# Arduino_HAT.net
KiCad netlist of a schematic drawn in EAGLE
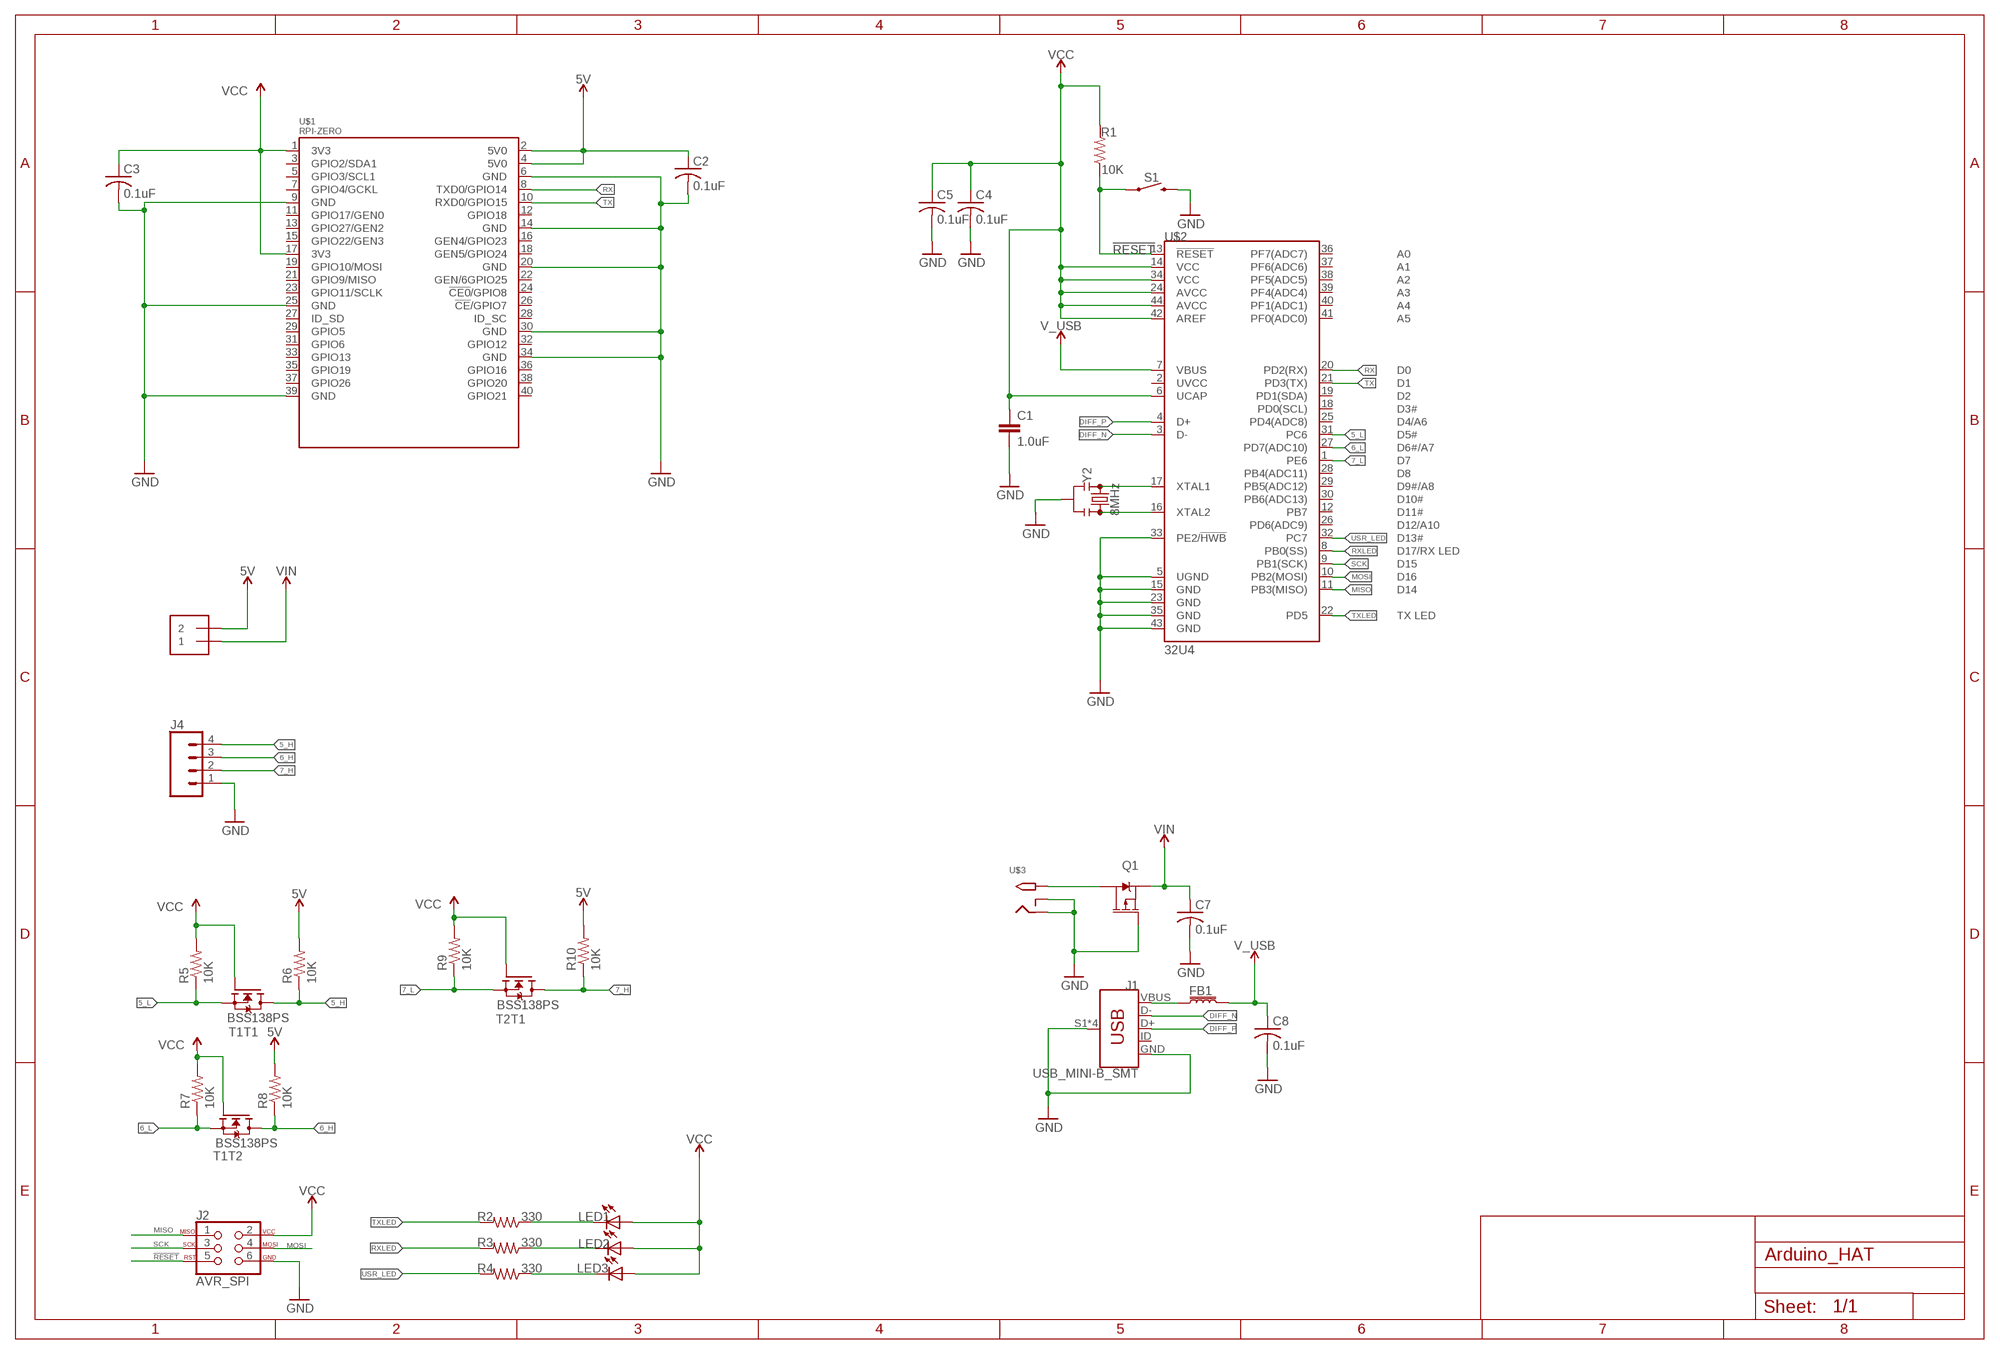
[diagram p0: schematic, sheet 1]

(export (version "E")
  (design (tool "Eeschema 10.0.6"))
  (components
    (comp (ref "C1")
      (value "1.0uF")
      (footprint "eagle-import:0805")
      (libsource (lib "eagle-import") (part "1.0UF-0805-25V-10%"))
    )
    (comp (ref "C2")
      (value "0.1uF")
      (footprint "eagle-import:C0805")
      (libsource (lib "eagle-import") (part "C-USC0805"))
    )
    (comp (ref "C3")
      (value "0.1uF")
      (footprint "eagle-import:C0805")
      (libsource (lib "eagle-import") (part "C-USC0805"))
    )
    (comp (ref "C4")
      (value "0.1uF")
      (footprint "eagle-import:C0805")
      (libsource (lib "eagle-import") (part "C-USC0805"))
    )
    (comp (ref "C5")
      (value "0.1uF")
      (footprint "eagle-import:C0805")
      (libsource (lib "eagle-import") (part "C-USC0805"))
    )
    (comp (ref "C7")
      (value "0.1uF")
      (footprint "eagle-import:C0805")
      (libsource (lib "eagle-import") (part "C-USC0805"))
    )
    (comp (ref "C8")
      (value "0.1uF")
      (footprint "eagle-import:C0805")
      (libsource (lib "eagle-import") (part "C-USC0805"))
    )
    (comp (ref "FB1")
      (value "30Ω/1.8A")
      (footprint "eagle-import:0603")
      (libsource (lib "eagle-import") (part "FERRITE_BEAD-0603"))
    )
    (comp (ref "J1")
      (value "USB_MINI-B_SMT")
      (footprint "eagle-import:USB-MINIB")
      (libsource (lib "eagle-import") (part "USB_MINI-B_SMT"))
    )
    (comp (ref "J2")
      (value "AVR_SPI")
      (footprint "eagle-import:2X3-NS")
      (libsource (lib "eagle-import") (part "AVR_SPI_PROG_3X2NS"))
    )
    (comp (ref "J3")
      (value "1X2-3.5MM")
      (footprint "eagle-import:1X2-3.5MM")
      (libsource (lib "eagle-import") (part "1X2-3.5MM"))
    )
    (comp (ref "J4")
      (value "CONN_04SCREW")
      (footprint "eagle-import:SCREWTERMINAL-3.5MM-4")
      (libsource (lib "eagle-import") (part "CONN_04SCREW"))
    )
    (comp (ref "LED1")
      (value "LEDCHIPLED_0805")
      (footprint "eagle-import:CHIPLED_0805")
      (libsource (lib "eagle-import") (part "LEDCHIPLED_0805"))
    )
    (comp (ref "LED2")
      (value "LEDCHIPLED_0805")
      (footprint "eagle-import:CHIPLED_0805")
      (libsource (lib "eagle-import") (part "LEDCHIPLED_0805"))
    )
    (comp (ref "LED3")
      (value "LEDCHIPLED_0805")
      (footprint "eagle-import:CHIPLED_0805")
      (libsource (lib "eagle-import") (part "LEDCHIPLED_0805"))
    )
    (comp (ref "Q1")
      (value "2.5A/30V/105mΩ")
      (footprint "eagle-import:SOT23-3")
      (libsource (lib "eagle-import") (part "MOSFET_PCH-DMG2307L"))
    )
    (comp (ref "R1")
      (value "10K")
      (footprint "eagle-import:0805")
      (libsource (lib "eagle-import") (part "RESISTOR0805"))
    )
    (comp (ref "R2")
      (value "330")
      (footprint "eagle-import:0805")
      (libsource (lib "eagle-import") (part "RESISTOR0805"))
    )
    (comp (ref "R3")
      (value "330")
      (footprint "eagle-import:0805")
      (libsource (lib "eagle-import") (part "RESISTOR0805"))
    )
    (comp (ref "R4")
      (value "330")
      (footprint "eagle-import:0805")
      (libsource (lib "eagle-import") (part "RESISTOR0805"))
    )
    (comp (ref "R5")
      (value "10K")
      (footprint "eagle-import:R0805")
      (libsource (lib "eagle-import") (part "R-US_R0805"))
    )
    (comp (ref "R6")
      (value "10K")
      (footprint "eagle-import:R0805")
      (libsource (lib "eagle-import") (part "R-US_R0805"))
    )
    (comp (ref "R7")
      (value "10K")
      (footprint "eagle-import:R0805")
      (libsource (lib "eagle-import") (part "R-US_R0805"))
    )
    (comp (ref "R8")
      (value "10K")
      (footprint "eagle-import:R0805")
      (libsource (lib "eagle-import") (part "R-US_R0805"))
    )
    (comp (ref "R9")
      (value "10K")
      (footprint "eagle-import:R0805")
      (libsource (lib "eagle-import") (part "R-US_R0805"))
    )
    (comp (ref "R10")
      (value "10K")
      (footprint "eagle-import:R0805")
      (libsource (lib "eagle-import") (part "R-US_R0805"))
    )
    (comp (ref "S1")
      (value "MOMENTARY-SWITCH-SPST-SMD-4.6X2.8MM")
      (footprint "eagle-import:TACTILE_SWITCH_SMD_4.6X2.8MM")
      (libsource (lib "eagle-import") (part "MOMENTARY-SWITCH-SPST-SMD-4.6X2.8MM"))
    )
    (comp (ref "T1")
      (value "BSS138PS")
      (footprint "eagle-import:SOT363")
      (libsource (lib "eagle-import") (part "BSS138PS"))
    )
    (comp (ref "T2")
      (value "BSS138PS")
      (footprint "eagle-import:SOT363")
      (libsource (lib "eagle-import") (part "BSS138PS"))
    )
    (comp (ref "U$1")
      (value "RPI-ZERO")
      (footprint "eagle-import:RASPBERRYPI_BASTELSTUBE_V13_RASPI_BOARD_B+_FULL")
      (libsource (lib "eagle-import") (part "RPI-ZERO"))
    )
    (comp (ref "U$2")
      (value "32U4")
      (footprint "eagle-import:QFN-44")
      (libsource (lib "eagle-import") (part "ATMEGA32U4QFN"))
    )
    (comp (ref "U$3")
      (value "2.1MMJACKTHM")
      (footprint "eagle-import:PJ-102A")
      (libsource (lib "eagle-import") (part "2.1MMJACKTHM"))
    )
    (comp (ref "Y2")
      (value "8MHz")
      (footprint "eagle-import:RESONATOR-SMD-3.2X1.3")
      (libsource (lib "eagle-import") (part "RESONATOR-8MHZSMD_3.2X1.3"))
    )
  )
  (nets
    (net (code "1") (name "/~{RESET}") (class "Default")
      (node (ref "J2") (pin "5") (pinfunction "5_5") (pintype "passive"))
      (node (ref "R1") (pin "1") (pinfunction "1_1") (pintype "passive"))
      (node (ref "S1") (pin "1") (pinfunction "1_1") (pintype "passive"))
      (node (ref "S1") (pin "2") (pinfunction "1_2") (pintype "passive"))
      (node (ref "U$2") (pin "13") (pinfunction "~{RESET}_13") (pintype "bidirectional"))
    )
    (net (code "2") (name "5V") (class "Default")
      (node (ref "C2") (pin "1") (pinfunction "1_1") (pintype "passive"))
      (node (ref "J3") (pin "2") (pinfunction "2_2") (pintype "passive"))
      (node (ref "R10") (pin "2") (pinfunction "2_2") (pintype "passive"))
      (node (ref "R6") (pin "2") (pinfunction "2_2") (pintype "passive"))
      (node (ref "R8") (pin "2") (pinfunction "2_2") (pintype "passive"))
      (node (ref "U$1") (pin "2") (pinfunction "5V0_2") (pintype "power_in"))
      (node (ref "U$1") (pin "4") (pinfunction "5V0_4") (pintype "power_in"))
    )
    (net (code "3") (name "5_H") (class "Default")
      (node (ref "J4") (pin "4") (pinfunction "GND_4") (pintype "passive"))
      (node (ref "R6") (pin "1") (pinfunction "1_1") (pintype "passive"))
      (node (ref "T1") (pin "6") (pinfunction "D_6") (pintype "passive"))
    )
    (net (code "4") (name "5_L") (class "Default")
      (node (ref "R5") (pin "1") (pinfunction "1_1") (pintype "passive"))
      (node (ref "T1") (pin "1") (pinfunction "S_1") (pintype "passive"))
      (node (ref "U$2") (pin "31") (pinfunction "PC6_31") (pintype "bidirectional"))
    )
    (net (code "5") (name "6_H") (class "Default")
      (node (ref "J4") (pin "3") (pinfunction "SDA_3") (pintype "passive"))
      (node (ref "R8") (pin "1") (pinfunction "1_1") (pintype "passive"))
      (node (ref "T1") (pin "3") (pinfunction "D_3") (pintype "passive"))
    )
    (net (code "6") (name "6_L") (class "Default")
      (node (ref "R7") (pin "1") (pinfunction "1_1") (pintype "passive"))
      (node (ref "T1") (pin "4") (pinfunction "S_4") (pintype "passive"))
      (node (ref "U$2") (pin "27") (pinfunction "PD7(ADC10)_27") (pintype "bidirectional"))
    )
    (net (code "7") (name "7_H") (class "Default")
      (node (ref "J4") (pin "2") (pinfunction "SCL_2") (pintype "passive"))
      (node (ref "R10") (pin "1") (pinfunction "1_1") (pintype "passive"))
      (node (ref "T2") (pin "6") (pinfunction "D_6") (pintype "passive"))
    )
    (net (code "8") (name "7_L") (class "Default")
      (node (ref "R9") (pin "1") (pinfunction "1_1") (pintype "passive"))
      (node (ref "T2") (pin "1") (pinfunction "S_1") (pintype "passive"))
      (node (ref "U$2") (pin "1") (pinfunction "PE6_1") (pintype "bidirectional"))
    )
    (net (code "9") (name "DIFF_N") (class "Default")
      (node (ref "J1") (pin "D-") (pinfunction "D-_D-") (pintype "bidirectional"))
      (node (ref "U$2") (pin "3") (pinfunction "D-_3") (pintype "bidirectional"))
    )
    (net (code "10") (name "DIFF_P") (class "Default")
      (node (ref "J1") (pin "D+") (pinfunction "D+_D+") (pintype "bidirectional"))
      (node (ref "U$2") (pin "4") (pinfunction "D+_4") (pintype "bidirectional"))
    )
    (net (code "11") (name "GND") (class "Default")
      (node (ref "C1") (pin "2") (pinfunction "2_2") (pintype "passive"))
      (node (ref "C2") (pin "2") (pinfunction "2_2") (pintype "passive"))
      (node (ref "C3") (pin "2") (pinfunction "2_2") (pintype "passive"))
      (node (ref "C4") (pin "2") (pinfunction "2_2") (pintype "passive"))
      (node (ref "C5") (pin "2") (pinfunction "2_2") (pintype "passive"))
      (node (ref "C7") (pin "2") (pinfunction "2_2") (pintype "passive"))
      (node (ref "C8") (pin "2") (pinfunction "2_2") (pintype "passive"))
      (node (ref "J1") (pin "GND") (pinfunction "GND_GND") (pintype "power_in"))
      (node (ref "J1") (pin "S1") (pinfunction "SHIELD_S1") (pintype "bidirectional"))
      (node (ref "J1") (pin "S2") (pinfunction "SHIELD_S2") (pintype "bidirectional"))
      (node (ref "J1") (pin "S3") (pinfunction "SHIELD_S3") (pintype "bidirectional"))
      (node (ref "J1") (pin "S4") (pinfunction "SHIELD_S4") (pintype "bidirectional"))
      (node (ref "J2") (pin "6") (pinfunction "6_6") (pintype "passive"))
      (node (ref "J4") (pin "1") (pinfunction "VCC_1") (pintype "passive"))
      (node (ref "Q1") (pin "1") (pinfunction "G_1") (pintype "bidirectional"))
      (node (ref "S1") (pin "3") (pinfunction "2_3") (pintype "passive"))
      (node (ref "S1") (pin "4") (pinfunction "2_4") (pintype "passive"))
      (node (ref "U$1") (pin "14") (pinfunction "GND_14") (pintype "power_in"))
      (node (ref "U$1") (pin "20") (pinfunction "GND_20") (pintype "power_in"))
      (node (ref "U$1") (pin "25") (pinfunction "GND_25") (pintype "power_in"))
      (node (ref "U$1") (pin "30") (pinfunction "GND_30") (pintype "power_in"))
      (node (ref "U$1") (pin "34") (pinfunction "GND_34") (pintype "power_in"))
      (node (ref "U$1") (pin "39") (pinfunction "GND_39") (pintype "power_in"))
      (node (ref "U$1") (pin "6") (pinfunction "GND_6") (pintype "power_in"))
      (node (ref "U$1") (pin "9") (pinfunction "GND_9") (pintype "power_in"))
      (node (ref "U$2") (pin "15") (pinfunction "GND_15") (pintype "bidirectional"))
      (node (ref "U$2") (pin "23") (pinfunction "GND_23") (pintype "bidirectional"))
      (node (ref "U$2") (pin "33") (pinfunction "PE2/~{HWB}_33") (pintype "bidirectional"))
      (node (ref "U$2") (pin "35") (pinfunction "GND_35") (pintype "bidirectional"))
      (node (ref "U$2") (pin "43") (pinfunction "GND_43") (pintype "bidirectional"))
      (node (ref "U$2") (pin "5") (pinfunction "UGND_5") (pintype "bidirectional"))
      (node (ref "U$3") (pin "RING") (pinfunction "RING_RING") (pintype "bidirectional"))
      (node (ref "U$3") (pin "RING_SW") (pinfunction "RING_SW_RING_SW") (pintype "bidirectional"))
      (node (ref "Y2") (pin "2") (pinfunction "2_2") (pintype "passive"))
    )
    (net (code "12") (name "MISO") (class "Default")
      (node (ref "J2") (pin "1") (pinfunction "1_1") (pintype "passive"))
      (node (ref "U$2") (pin "11") (pinfunction "PB3(MISO)_11") (pintype "bidirectional"))
    )
    (net (code "13") (name "MOSI") (class "Default")
      (node (ref "J2") (pin "4") (pinfunction "4_4") (pintype "passive"))
      (node (ref "U$2") (pin "10") (pinfunction "PB2(MOSI)_10") (pintype "bidirectional"))
    )
    (net (code "14") (name "Net-(FB1-Pad1)") (class "Default")
      (node (ref "FB1") (pin "1") (pinfunction "1_1") (pintype "passive"))
      (node (ref "J1") (pin "VBUS") (pinfunction "VBUS_VBUS") (pintype "power_in"))
    )
    (net (code "15") (name "Net-(LED1-PadC)") (class "Default")
      (node (ref "LED1") (pin "C") (pinfunction "C_C") (pintype "passive"))
      (node (ref "R2") (pin "1") (pinfunction "1_1") (pintype "passive"))
    )
    (net (code "16") (name "Net-(LED2-PadC)") (class "Default")
      (node (ref "LED2") (pin "C") (pinfunction "C_C") (pintype "passive"))
      (node (ref "R3") (pin "1") (pinfunction "1_1") (pintype "passive"))
    )
    (net (code "17") (name "Net-(LED3-PadC)") (class "Default")
      (node (ref "LED3") (pin "C") (pinfunction "C_C") (pintype "passive"))
      (node (ref "R4") (pin "1") (pinfunction "1_1") (pintype "passive"))
    )
    (net (code "18") (name "Net-(Q1-D)") (class "Default")
      (node (ref "Q1") (pin "3") (pinfunction "D_3") (pintype "bidirectional"))
      (node (ref "U$3") (pin "TIP") (pinfunction "TIP_TIP") (pintype "bidirectional"))
    )
    (net (code "19") (name "Net-(U$2-XTAL1)") (class "Default")
      (node (ref "U$2") (pin "17") (pinfunction "XTAL1_17") (pintype "bidirectional"))
      (node (ref "Y2") (pin "1") (pinfunction "1_1") (pintype "passive"))
    )
    (net (code "20") (name "Net-(U$2-XTAL2)") (class "Default")
      (node (ref "U$2") (pin "16") (pinfunction "XTAL2_16") (pintype "bidirectional"))
      (node (ref "Y2") (pin "3") (pinfunction "3_3") (pintype "passive"))
    )
    (net (code "21") (name "RX") (class "Default")
      (node (ref "U$1") (pin "8") (pinfunction "TXD0/GPIO14_8") (pintype "bidirectional"))
      (node (ref "U$2") (pin "20") (pinfunction "PD2(RX)_20") (pintype "bidirectional"))
    )
    (net (code "22") (name "RXLED") (class "Default")
      (node (ref "R3") (pin "2") (pinfunction "2_2") (pintype "passive"))
      (node (ref "U$2") (pin "8") (pinfunction "PB0(SS)_8") (pintype "bidirectional"))
    )
    (net (code "23") (name "SCK") (class "Default")
      (node (ref "J2") (pin "3") (pinfunction "3_3") (pintype "passive"))
      (node (ref "U$2") (pin "9") (pinfunction "PB1(SCK)_9") (pintype "bidirectional"))
    )
    (net (code "24") (name "TX") (class "Default")
      (node (ref "U$1") (pin "10") (pinfunction "RXD0/GPIO15_10") (pintype "bidirectional"))
      (node (ref "U$2") (pin "21") (pinfunction "PD3(TX)_21") (pintype "bidirectional"))
    )
    (net (code "25") (name "TXLED") (class "Default")
      (node (ref "R2") (pin "2") (pinfunction "2_2") (pintype "passive"))
      (node (ref "U$2") (pin "22") (pinfunction "PD5_22") (pintype "bidirectional"))
    )
    (net (code "26") (name "USR_LED") (class "Default")
      (node (ref "R4") (pin "2") (pinfunction "2_2") (pintype "passive"))
      (node (ref "U$2") (pin "32") (pinfunction "PC7_32") (pintype "bidirectional"))
    )
    (net (code "27") (name "VCC") (class "Default")
      (node (ref "C1") (pin "1") (pinfunction "1_1") (pintype "passive"))
      (node (ref "C3") (pin "1") (pinfunction "1_1") (pintype "passive"))
      (node (ref "C4") (pin "1") (pinfunction "1_1") (pintype "passive"))
      (node (ref "C5") (pin "1") (pinfunction "1_1") (pintype "passive"))
      (node (ref "J2") (pin "2") (pinfunction "2_2") (pintype "passive"))
      (node (ref "LED1") (pin "A") (pinfunction "A_A") (pintype "passive"))
      (node (ref "LED2") (pin "A") (pinfunction "A_A") (pintype "passive"))
      (node (ref "LED3") (pin "A") (pinfunction "A_A") (pintype "passive"))
      (node (ref "R1") (pin "2") (pinfunction "2_2") (pintype "passive"))
      (node (ref "R5") (pin "2") (pinfunction "2_2") (pintype "passive"))
      (node (ref "R7") (pin "2") (pinfunction "2_2") (pintype "passive"))
      (node (ref "R9") (pin "2") (pinfunction "2_2") (pintype "passive"))
      (node (ref "T1") (pin "2") (pinfunction "G_2") (pintype "passive"))
      (node (ref "T1") (pin "5") (pinfunction "G_5") (pintype "passive"))
      (node (ref "T2") (pin "2") (pinfunction "G_2") (pintype "passive"))
      (node (ref "U$1") (pin "1") (pinfunction "3V3_1") (pintype "power_in"))
      (node (ref "U$1") (pin "17") (pinfunction "3V3_17") (pintype "power_in"))
      (node (ref "U$2") (pin "14") (pinfunction "VCC_14") (pintype "bidirectional"))
      (node (ref "U$2") (pin "24") (pinfunction "AVCC_24") (pintype "bidirectional"))
      (node (ref "U$2") (pin "34") (pinfunction "VCC_34") (pintype "bidirectional"))
      (node (ref "U$2") (pin "42") (pinfunction "AREF_42") (pintype "bidirectional"))
      (node (ref "U$2") (pin "44") (pinfunction "AVCC_44") (pintype "bidirectional"))
      (node (ref "U$2") (pin "6") (pinfunction "UCAP_6") (pintype "bidirectional"))
    )
    (net (code "28") (name "VIN") (class "Default")
      (node (ref "C7") (pin "1") (pinfunction "1_1") (pintype "passive"))
      (node (ref "J3") (pin "1") (pinfunction "1_1") (pintype "passive"))
      (node (ref "Q1") (pin "2") (pinfunction "S_2") (pintype "bidirectional"))
    )
    (net (code "29") (name "V_USB") (class "Default")
      (node (ref "C8") (pin "1") (pinfunction "1_1") (pintype "passive"))
      (node (ref "FB1") (pin "2") (pinfunction "2_2") (pintype "passive"))
      (node (ref "U$2") (pin "7") (pinfunction "VBUS_7") (pintype "bidirectional"))
    )
    (net (code "30") (name "unconnected-(J1-PadID)") (class "Default")
      (node (ref "J1") (pin "ID") (pinfunction "ID_ID") (pintype "bidirectional"))
    )
    (net (code "31") (name "unconnected-(U$1-GEN4{slash}GPIO23-Pad16)") (class "Default")
      (node (ref "U$1") (pin "16") (pinfunction "GEN4/GPIO23_16") (pintype "bidirectional"))
    )
    (net (code "32") (name "unconnected-(U$1-GEN5{slash}GPIO24-Pad18)") (class "Default")
      (node (ref "U$1") (pin "18") (pinfunction "GEN5/GPIO24_18") (pintype "bidirectional"))
    )
    (net (code "33") (name "unconnected-(U$1-GEN{slash}6GPIO25-Pad22)") (class "Default")
      (node (ref "U$1") (pin "22") (pinfunction "GEN/6GPIO25_22") (pintype "bidirectional"))
    )
    (net (code "34") (name "unconnected-(U$1-GPIO2{slash}SDA1-Pad3)") (class "Default")
      (node (ref "U$1") (pin "3") (pinfunction "GPIO2/SDA1_3") (pintype "bidirectional"))
    )
    (net (code "35") (name "unconnected-(U$1-GPIO3{slash}SCL1-Pad5)") (class "Default")
      (node (ref "U$1") (pin "5") (pinfunction "GPIO3/SCL1_5") (pintype "bidirectional"))
    )
    (net (code "36") (name "unconnected-(U$1-GPIO4{slash}GCKL-Pad7)") (class "Default")
      (node (ref "U$1") (pin "7") (pinfunction "GPIO4/GCKL_7") (pintype "bidirectional"))
    )
    (net (code "37") (name "unconnected-(U$1-GPIO5-Pad29)") (class "Default")
      (node (ref "U$1") (pin "29") (pinfunction "GPIO5_29") (pintype "bidirectional"))
    )
    (net (code "38") (name "unconnected-(U$1-GPIO6-Pad31)") (class "Default")
      (node (ref "U$1") (pin "31") (pinfunction "GPIO6_31") (pintype "bidirectional"))
    )
    (net (code "39") (name "unconnected-(U$1-GPIO9{slash}MISO-Pad21)") (class "Default")
      (node (ref "U$1") (pin "21") (pinfunction "GPIO9/MISO_21") (pintype "bidirectional"))
    )
    (net (code "40") (name "unconnected-(U$1-GPIO10{slash}MOSI-Pad19)") (class "Default")
      (node (ref "U$1") (pin "19") (pinfunction "GPIO10/MOSI_19") (pintype "bidirectional"))
    )
    (net (code "41") (name "unconnected-(U$1-GPIO11{slash}SCLK-Pad23)") (class "Default")
      (node (ref "U$1") (pin "23") (pinfunction "GPIO11/SCLK_23") (pintype "bidirectional"))
    )
    (net (code "42") (name "unconnected-(U$1-GPIO12-Pad32)") (class "Default")
      (node (ref "U$1") (pin "32") (pinfunction "GPIO12_32") (pintype "bidirectional"))
    )
    (net (code "43") (name "unconnected-(U$1-GPIO13-Pad33)") (class "Default")
      (node (ref "U$1") (pin "33") (pinfunction "GPIO13_33") (pintype "bidirectional"))
    )
    (net (code "44") (name "unconnected-(U$1-GPIO16-Pad36)") (class "Default")
      (node (ref "U$1") (pin "36") (pinfunction "GPIO16_36") (pintype "bidirectional"))
    )
    (net (code "45") (name "unconnected-(U$1-GPIO17{slash}GEN0-Pad11)") (class "Default")
      (node (ref "U$1") (pin "11") (pinfunction "GPIO17/GEN0_11") (pintype "bidirectional"))
    )
    (net (code "46") (name "unconnected-(U$1-GPIO18-Pad12)") (class "Default")
      (node (ref "U$1") (pin "12") (pinfunction "GPIO18_12") (pintype "bidirectional"))
    )
    (net (code "47") (name "unconnected-(U$1-GPIO19-Pad35)") (class "Default")
      (node (ref "U$1") (pin "35") (pinfunction "GPIO19_35") (pintype "bidirectional"))
    )
    (net (code "48") (name "unconnected-(U$1-GPIO20-Pad38)") (class "Default")
      (node (ref "U$1") (pin "38") (pinfunction "GPIO20_38") (pintype "bidirectional"))
    )
    (net (code "49") (name "unconnected-(U$1-GPIO21-Pad40)") (class "Default")
      (node (ref "U$1") (pin "40") (pinfunction "GPIO21_40") (pintype "bidirectional"))
    )
    (net (code "50") (name "unconnected-(U$1-GPIO22{slash}GEN3-Pad15)") (class "Default")
      (node (ref "U$1") (pin "15") (pinfunction "GPIO22/GEN3_15") (pintype "bidirectional"))
    )
    (net (code "51") (name "unconnected-(U$1-GPIO26-Pad37)") (class "Default")
      (node (ref "U$1") (pin "37") (pinfunction "GPIO26_37") (pintype "bidirectional"))
    )
    (net (code "52") (name "unconnected-(U$1-GPIO27{slash}GEN2-Pad13)") (class "Default")
      (node (ref "U$1") (pin "13") (pinfunction "GPIO27/GEN2_13") (pintype "bidirectional"))
    )
    (net (code "53") (name "unconnected-(U$1-ID_SC-Pad28)") (class "Default")
      (node (ref "U$1") (pin "28") (pinfunction "ID_SC_28") (pintype "bidirectional"))
    )
    (net (code "54") (name "unconnected-(U$1-ID_SD-Pad27)") (class "Default")
      (node (ref "U$1") (pin "27") (pinfunction "ID_SD_27") (pintype "bidirectional"))
    )
    (net (code "55") (name "unconnected-(U$1-~{CE0}{slash}GPIO8-Pad24)") (class "Default")
      (node (ref "U$1") (pin "24") (pinfunction "~{CE0}/GPIO8_24") (pintype "bidirectional"))
    )
    (net (code "56") (name "unconnected-(U$1-~{CE}{slash}GPIO7-Pad26)") (class "Default")
      (node (ref "U$1") (pin "26") (pinfunction "~{CE}/GPIO7_26") (pintype "bidirectional"))
    )
    (net (code "57") (name "unconnected-(U$2-PB4(ADC11)-Pad28)") (class "Default")
      (node (ref "U$2") (pin "28") (pinfunction "PB4(ADC11)_28") (pintype "bidirectional"))
    )
    (net (code "58") (name "unconnected-(U$2-PB5(ADC12)-Pad29)") (class "Default")
      (node (ref "U$2") (pin "29") (pinfunction "PB5(ADC12)_29") (pintype "bidirectional"))
    )
    (net (code "59") (name "unconnected-(U$2-PB6(ADC13)-Pad30)") (class "Default")
      (node (ref "U$2") (pin "30") (pinfunction "PB6(ADC13)_30") (pintype "bidirectional"))
    )
    (net (code "60") (name "unconnected-(U$2-PB7-Pad12)") (class "Default")
      (node (ref "U$2") (pin "12") (pinfunction "PB7_12") (pintype "bidirectional"))
    )
    (net (code "61") (name "unconnected-(U$2-PD0(SCL)-Pad18)") (class "Default")
      (node (ref "U$2") (pin "18") (pinfunction "PD0(SCL)_18") (pintype "bidirectional"))
    )
    (net (code "62") (name "unconnected-(U$2-PD1(SDA)-Pad19)") (class "Default")
      (node (ref "U$2") (pin "19") (pinfunction "PD1(SDA)_19") (pintype "bidirectional"))
    )
    (net (code "63") (name "unconnected-(U$2-PD4(ADC8)-Pad25)") (class "Default")
      (node (ref "U$2") (pin "25") (pinfunction "PD4(ADC8)_25") (pintype "bidirectional"))
    )
    (net (code "64") (name "unconnected-(U$2-PD6(ADC9)-Pad26)") (class "Default")
      (node (ref "U$2") (pin "26") (pinfunction "PD6(ADC9)_26") (pintype "bidirectional"))
    )
    (net (code "65") (name "unconnected-(U$2-PF0(ADC0)-Pad41)") (class "Default")
      (node (ref "U$2") (pin "41") (pinfunction "PF0(ADC0)_41") (pintype "bidirectional"))
    )
    (net (code "66") (name "unconnected-(U$2-PF1(ADC1)-Pad40)") (class "Default")
      (node (ref "U$2") (pin "40") (pinfunction "PF1(ADC1)_40") (pintype "bidirectional"))
    )
    (net (code "67") (name "unconnected-(U$2-PF4(ADC4)-Pad39)") (class "Default")
      (node (ref "U$2") (pin "39") (pinfunction "PF4(ADC4)_39") (pintype "bidirectional"))
    )
    (net (code "68") (name "unconnected-(U$2-PF5(ADC5)-Pad38)") (class "Default")
      (node (ref "U$2") (pin "38") (pinfunction "PF5(ADC5)_38") (pintype "bidirectional"))
    )
    (net (code "69") (name "unconnected-(U$2-PF6(ADC6)-Pad37)") (class "Default")
      (node (ref "U$2") (pin "37") (pinfunction "PF6(ADC6)_37") (pintype "bidirectional"))
    )
    (net (code "70") (name "unconnected-(U$2-PF7(ADC7)-Pad36)") (class "Default")
      (node (ref "U$2") (pin "36") (pinfunction "PF7(ADC7)_36") (pintype "bidirectional"))
    )
    (net (code "71") (name "unconnected-(U$2-UVCC-Pad2)") (class "Default")
      (node (ref "U$2") (pin "2") (pinfunction "UVCC_2") (pintype "bidirectional"))
    )
  )
)
